# FeatherUSBSerial.net
KiCad netlist of a schematic drawn in EAGLE
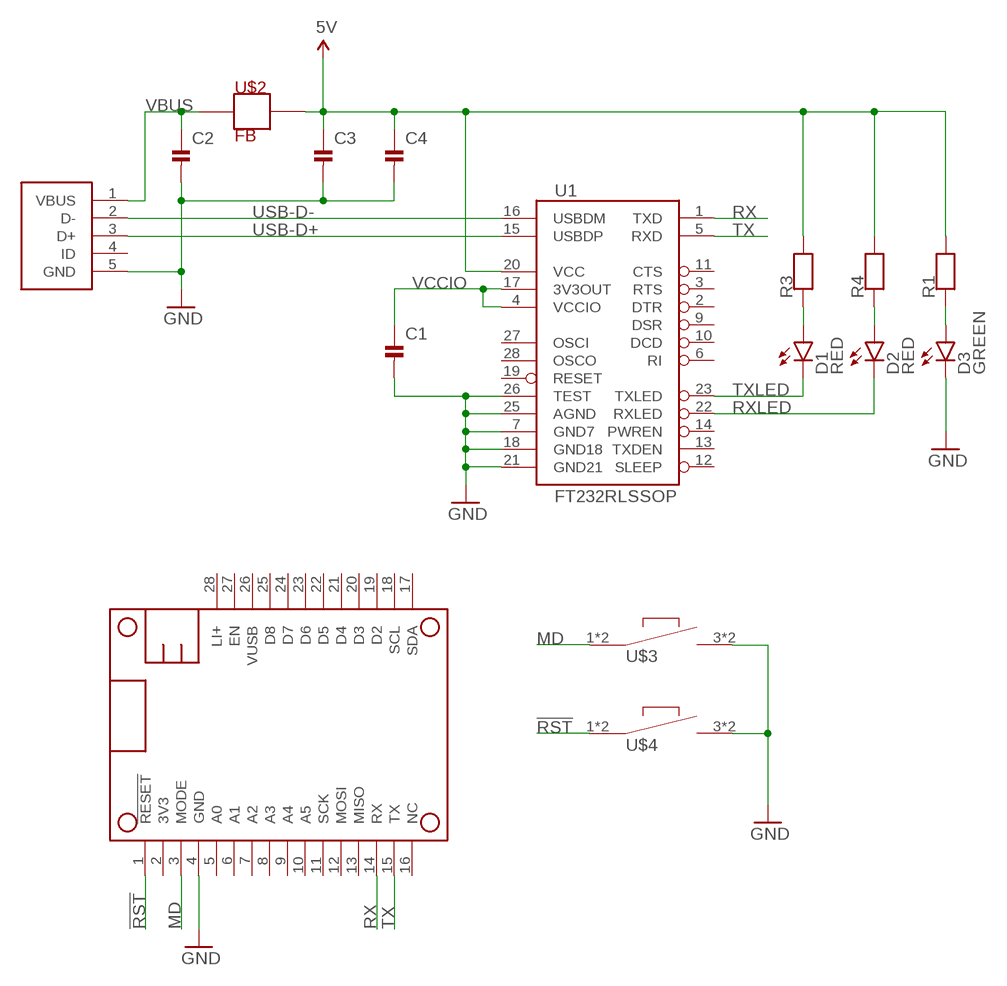
[diagram p0: schematic, sheet 1]

(export (version "E")
  (design (tool "Eeschema 10.0.6"))
  (components
    (comp (ref "C1")
      (value "0.1uF")
      (footprint "eagle-import:_0805MP")
      (libsource (lib "eagle-import") (part "CAP_CERAMIC_0805MP"))
    )
    (comp (ref "C2")
      (value "0.01uF")
      (footprint "eagle-import:_0805MP")
      (libsource (lib "eagle-import") (part "CAP_CERAMIC_0805MP"))
    )
    (comp (ref "C3")
      (value "0.1uF")
      (footprint "eagle-import:_0805MP")
      (libsource (lib "eagle-import") (part "CAP_CERAMIC_0805MP"))
    )
    (comp (ref "C4")
      (value "4.7uF")
      (footprint "eagle-import:_0805MP")
      (libsource (lib "eagle-import") (part "CAP_CERAMIC_0805MP"))
    )
    (comp (ref "D1")
      (value "RED")
      (footprint "eagle-import:LED-0603")
      (libsource (lib "eagle-import") (part "LED-RED"))
    )
    (comp (ref "D2")
      (value "RED")
      (footprint "eagle-import:LED-0603")
      (libsource (lib "eagle-import") (part "LED-RED"))
    )
    (comp (ref "D3")
      (value "GREEN")
      (footprint "eagle-import:LED-0603")
      (libsource (lib "eagle-import") (part "LED-GREEN0603"))
    )
    (comp (ref "MS1")
      (value "FEATHERWING_NODIM")
      (footprint "eagle-import:FEATHERWING_NODIM")
      (libsource (lib "eagle-import") (part "FEATHERWING_NODIM"))
    )
    (comp (ref "R1")
      (value "680")
      (footprint "eagle-import:0805-NO")
      (libsource (lib "eagle-import") (part "RESISTOR0805_NOOUTLINE"))
    )
    (comp (ref "R3")
      (value "680")
      (footprint "eagle-import:0805-NO")
      (libsource (lib "eagle-import") (part "RESISTOR0805_NOOUTLINE"))
    )
    (comp (ref "R4")
      (value "680")
      (footprint "eagle-import:0805-NO")
      (libsource (lib "eagle-import") (part "RESISTOR0805_NOOUTLINE"))
    )
    (comp (ref "U$1")
      (value "USB-MICRO-B-SOCKET-AMPHENOL")
      (footprint "eagle-import:USB-B-SMT-AMPHENOL")
      (libsource (lib "eagle-import") (part "USB-MICRO-B-SOCKET-AMPHENOL"))
    )
    (comp (ref "U$2")
      (value "FB")
      (footprint "eagle-import:0805")
      (libsource (lib "eagle-import") (part "FERRITE-BEAD-MI0805K400R-10"))
    )
    (comp (ref "U$3")
      (value "TL3300CFXXXQ")
      (footprint "eagle-import:12MM_TACTILE")
      (fields (field (name "MPN") "TL3300CF160Q"))
      (libsource (lib "eagle-import") (part "TL3300CFXXXQ"))
    )
    (comp (ref "U$4")
      (value "TL3300CFXXXQ")
      (footprint "eagle-import:12MM_TACTILE")
      (fields (field (name "MPN") "TL3300CF160Q"))
      (libsource (lib "eagle-import") (part "TL3300CFXXXQ"))
    )
    (comp (ref "U1")
      (value "FT232RLSSOP")
      (footprint "eagle-import:SSOP28DB")
      (libsource (lib "eagle-import") (part "FT232RLSSOP"))
    )
  )
  (nets
    (net (code "1") (name "/3V3") (class "Default")
      (node (ref "MS1") (pin "2") (pinfunction "3V3_2") (pintype "power_in"))
    )
    (net (code "2") (name "/LI+") (class "Default")
      (node (ref "MS1") (pin "28") (pinfunction "LI+_28") (pintype "power_in"))
    )
    (net (code "3") (name "/MD") (class "Default")
      (node (ref "MS1") (pin "3") (pinfunction "MODE_3") (pintype "passive"))
      (node (ref "U$3") (pin "1") (pinfunction "P$1_1") (pintype "bidirectional"))
      (node (ref "U$3") (pin "2") (pinfunction "P$1_2") (pintype "bidirectional"))
    )
    (net (code "4") (name "/RX") (class "Default")
      (node (ref "MS1") (pin "14") (pinfunction "RX_14") (pintype "bidirectional"))
      (node (ref "U1") (pin "1") (pinfunction "TXD_1") (pintype "output"))
    )
    (net (code "5") (name "/RXLED") (class "Default")
      (node (ref "D2") (pin "C") (pinfunction "C_C") (pintype "passive"))
      (node (ref "U1") (pin "22") (pinfunction "RXLED_22") (pintype "input"))
    )
    (net (code "6") (name "/TX") (class "Default")
      (node (ref "MS1") (pin "15") (pinfunction "TX_15") (pintype "bidirectional"))
      (node (ref "U1") (pin "5") (pinfunction "RXD_5") (pintype "input"))
    )
    (net (code "7") (name "/TXLED") (class "Default")
      (node (ref "D1") (pin "C") (pinfunction "C_C") (pintype "passive"))
      (node (ref "U1") (pin "23") (pinfunction "TXLED_23") (pintype "input"))
    )
    (net (code "8") (name "/USB-D+") (class "Default")
      (node (ref "U$1") (pin "3") (pinfunction "D+_3") (pintype "passive"))
      (node (ref "U1") (pin "15") (pinfunction "USBDP_15") (pintype "bidirectional"))
    )
    (net (code "9") (name "/USB-D-") (class "Default")
      (node (ref "U$1") (pin "2") (pinfunction "D-_2") (pintype "passive"))
      (node (ref "U1") (pin "16") (pinfunction "USBDM_16") (pintype "bidirectional"))
    )
    (net (code "10") (name "/VBUS") (class "Default")
      (node (ref "C2") (pin "1") (pinfunction "1_1") (pintype "passive"))
      (node (ref "U$1") (pin "1") (pinfunction "VBUS_1") (pintype "passive"))
      (node (ref "U$2") (pin "1") (pinfunction "1_1") (pintype "passive"))
    )
    (net (code "11") (name "/VCCIO") (class "Default")
      (node (ref "C1") (pin "1") (pinfunction "1_1") (pintype "passive"))
      (node (ref "U1") (pin "17") (pinfunction "3V3OUT_17") (pintype "output"))
      (node (ref "U1") (pin "4") (pinfunction "VCCIO_4") (pintype "power_in"))
    )
    (net (code "12") (name "/VUSB") (class "Default")
      (node (ref "MS1") (pin "26") (pinfunction "VUSB_26") (pintype "power_in"))
    )
    (net (code "13") (name "/~{RST}") (class "Default")
      (node (ref "MS1") (pin "1") (pinfunction "~{RESET}_1") (pintype "input"))
      (node (ref "U$4") (pin "1") (pinfunction "P$1_1") (pintype "bidirectional"))
      (node (ref "U$4") (pin "2") (pinfunction "P$1_2") (pintype "bidirectional"))
    )
    (net (code "14") (name "5V") (class "Default")
      (node (ref "C3") (pin "1") (pinfunction "1_1") (pintype "passive"))
      (node (ref "C4") (pin "1") (pinfunction "1_1") (pintype "passive"))
      (node (ref "R1") (pin "2") (pinfunction "2_2") (pintype "passive"))
      (node (ref "R3") (pin "2") (pinfunction "2_2") (pintype "passive"))
      (node (ref "R4") (pin "2") (pinfunction "2_2") (pintype "passive"))
      (node (ref "U$2") (pin "2") (pinfunction "2_2") (pintype "passive"))
      (node (ref "U1") (pin "20") (pinfunction "VCC_20") (pintype "power_in"))
    )
    (net (code "15") (name "GND") (class "Default")
      (node (ref "C1") (pin "2") (pinfunction "2_2") (pintype "passive"))
      (node (ref "C2") (pin "2") (pinfunction "2_2") (pintype "passive"))
      (node (ref "C3") (pin "2") (pinfunction "2_2") (pintype "passive"))
      (node (ref "C4") (pin "2") (pinfunction "2_2") (pintype "passive"))
      (node (ref "D3") (pin "C") (pinfunction "C_C") (pintype "passive"))
      (node (ref "MS1") (pin "4") (pinfunction "GND_4") (pintype "power_in"))
      (node (ref "U$1") (pin "5") (pinfunction "GND_5") (pintype "passive"))
      (node (ref "U$3") (pin "3") (pinfunction "P$2_3") (pintype "bidirectional"))
      (node (ref "U$3") (pin "4") (pinfunction "P$2_4") (pintype "bidirectional"))
      (node (ref "U$4") (pin "3") (pinfunction "P$2_3") (pintype "bidirectional"))
      (node (ref "U$4") (pin "4") (pinfunction "P$2_4") (pintype "bidirectional"))
      (node (ref "U1") (pin "18") (pinfunction "GND18_18") (pintype "power_in"))
      (node (ref "U1") (pin "21") (pinfunction "GND21_21") (pintype "power_in"))
      (node (ref "U1") (pin "25") (pinfunction "AGND_25") (pintype "power_in"))
      (node (ref "U1") (pin "26") (pinfunction "TEST_26") (pintype "input"))
      (node (ref "U1") (pin "7") (pinfunction "GND7_7") (pintype "power_in"))
    )
    (net (code "16") (name "Net-(D1-PadA)") (class "Default")
      (node (ref "D1") (pin "A") (pinfunction "A_A") (pintype "passive"))
      (node (ref "R3") (pin "1") (pinfunction "1_1") (pintype "passive"))
    )
    (net (code "17") (name "Net-(D2-PadA)") (class "Default")
      (node (ref "D2") (pin "A") (pinfunction "A_A") (pintype "passive"))
      (node (ref "R4") (pin "1") (pinfunction "1_1") (pintype "passive"))
    )
    (net (code "18") (name "Net-(D3-PadA)") (class "Default")
      (node (ref "D3") (pin "A") (pinfunction "A_A") (pintype "passive"))
      (node (ref "R1") (pin "1") (pinfunction "1_1") (pintype "passive"))
    )
    (net (code "19") (name "unconnected-(MS1-A0-Pad5)") (class "Default")
      (node (ref "MS1") (pin "5") (pinfunction "A0_5") (pintype "bidirectional"))
    )
    (net (code "20") (name "unconnected-(MS1-A1-Pad6)") (class "Default")
      (node (ref "MS1") (pin "6") (pinfunction "A1_6") (pintype "bidirectional"))
    )
    (net (code "21") (name "unconnected-(MS1-A2-Pad7)") (class "Default")
      (node (ref "MS1") (pin "7") (pinfunction "A2_7") (pintype "bidirectional"))
    )
    (net (code "22") (name "unconnected-(MS1-A3-Pad8)") (class "Default")
      (node (ref "MS1") (pin "8") (pinfunction "A3_8") (pintype "bidirectional"))
    )
    (net (code "23") (name "unconnected-(MS1-A4-Pad9)") (class "Default")
      (node (ref "MS1") (pin "9") (pinfunction "A4_9") (pintype "bidirectional"))
    )
    (net (code "24") (name "unconnected-(MS1-A5-Pad10)") (class "Default")
      (node (ref "MS1") (pin "10") (pinfunction "A5_10") (pintype "bidirectional"))
    )
    (net (code "25") (name "unconnected-(MS1-D2-Pad19)") (class "Default")
      (node (ref "MS1") (pin "19") (pinfunction "D2_19") (pintype "bidirectional"))
    )
    (net (code "26") (name "unconnected-(MS1-D3-Pad20)") (class "Default")
      (node (ref "MS1") (pin "20") (pinfunction "D3_20") (pintype "bidirectional"))
    )
    (net (code "27") (name "unconnected-(MS1-D4-Pad21)") (class "Default")
      (node (ref "MS1") (pin "21") (pinfunction "D4_21") (pintype "bidirectional"))
    )
    (net (code "28") (name "unconnected-(MS1-D5-Pad22)") (class "Default")
      (node (ref "MS1") (pin "22") (pinfunction "D5_22") (pintype "bidirectional"))
    )
    (net (code "29") (name "unconnected-(MS1-D6-Pad23)") (class "Default")
      (node (ref "MS1") (pin "23") (pinfunction "D6_23") (pintype "bidirectional"))
    )
    (net (code "30") (name "unconnected-(MS1-D7-Pad24)") (class "Default")
      (node (ref "MS1") (pin "24") (pinfunction "D7_24") (pintype "bidirectional"))
    )
    (net (code "31") (name "unconnected-(MS1-D8-Pad25)") (class "Default")
      (node (ref "MS1") (pin "25") (pinfunction "D8_25") (pintype "bidirectional"))
    )
    (net (code "32") (name "unconnected-(MS1-EN-Pad27)") (class "Default")
      (node (ref "MS1") (pin "27") (pinfunction "EN_27") (pintype "passive"))
    )
    (net (code "33") (name "unconnected-(MS1-MISO-Pad13)") (class "Default")
      (node (ref "MS1") (pin "13") (pinfunction "MISO_13") (pintype "bidirectional"))
    )
    (net (code "34") (name "unconnected-(MS1-MOSI-Pad12)") (class "Default")
      (node (ref "MS1") (pin "12") (pinfunction "MOSI_12") (pintype "bidirectional"))
    )
    (net (code "35") (name "unconnected-(MS1-NC-Pad16)") (class "Default")
      (node (ref "MS1") (pin "16") (pinfunction "NC_16") (pintype "passive"))
    )
    (net (code "36") (name "unconnected-(MS1-SCK-Pad11)") (class "Default")
      (node (ref "MS1") (pin "11") (pinfunction "SCK_11") (pintype "bidirectional"))
    )
    (net (code "37") (name "unconnected-(MS1-SCL-Pad18)") (class "Default")
      (node (ref "MS1") (pin "18") (pinfunction "SCL_18") (pintype "bidirectional"))
    )
    (net (code "38") (name "unconnected-(MS1-SDA-Pad17)") (class "Default")
      (node (ref "MS1") (pin "17") (pinfunction "SDA_17") (pintype "bidirectional"))
    )
    (net (code "39") (name "unconnected-(U$1-ID-Pad4)") (class "Default")
      (node (ref "U$1") (pin "4") (pinfunction "ID_4") (pintype "passive"))
    )
    (net (code "40") (name "unconnected-(U1-CTS-Pad11)") (class "Default")
      (node (ref "U1") (pin "11") (pinfunction "CTS_11") (pintype "input"))
    )
    (net (code "41") (name "unconnected-(U1-DCD-Pad10)") (class "Default")
      (node (ref "U1") (pin "10") (pinfunction "DCD_10") (pintype "input"))
    )
    (net (code "42") (name "unconnected-(U1-DSR-Pad9)") (class "Default")
      (node (ref "U1") (pin "9") (pinfunction "DSR_9") (pintype "input"))
    )
    (net (code "43") (name "unconnected-(U1-DTR-Pad2)") (class "Default")
      (node (ref "U1") (pin "2") (pinfunction "DTR_2") (pintype "output"))
    )
    (net (code "44") (name "unconnected-(U1-OSCI-Pad27)") (class "Default")
      (node (ref "U1") (pin "27") (pinfunction "OSCI_27") (pintype "input"))
    )
    (net (code "45") (name "unconnected-(U1-OSCO-Pad28)") (class "Default")
      (node (ref "U1") (pin "28") (pinfunction "OSCO_28") (pintype "output"))
    )
    (net (code "46") (name "unconnected-(U1-PWREN-Pad14)") (class "Default")
      (node (ref "U1") (pin "14") (pinfunction "PWREN_14") (pintype "input"))
    )
    (net (code "47") (name "unconnected-(U1-RESET-Pad19)") (class "Default")
      (node (ref "U1") (pin "19") (pinfunction "RESET_19") (pintype "input"))
    )
    (net (code "48") (name "unconnected-(U1-RI-Pad6)") (class "Default")
      (node (ref "U1") (pin "6") (pinfunction "RI_6") (pintype "input"))
    )
    (net (code "49") (name "unconnected-(U1-RTS-Pad3)") (class "Default")
      (node (ref "U1") (pin "3") (pinfunction "RTS_3") (pintype "output"))
    )
    (net (code "50") (name "unconnected-(U1-SLEEP-Pad12)") (class "Default")
      (node (ref "U1") (pin "12") (pinfunction "SLEEP_12") (pintype "input"))
    )
    (net (code "51") (name "unconnected-(U1-TXDEN-Pad13)") (class "Default")
      (node (ref "U1") (pin "13") (pinfunction "TXDEN_13") (pintype "input"))
    )
  )
)
